# psvsd-v20.net
KiCad netlist of a schematic drawn in EAGLE
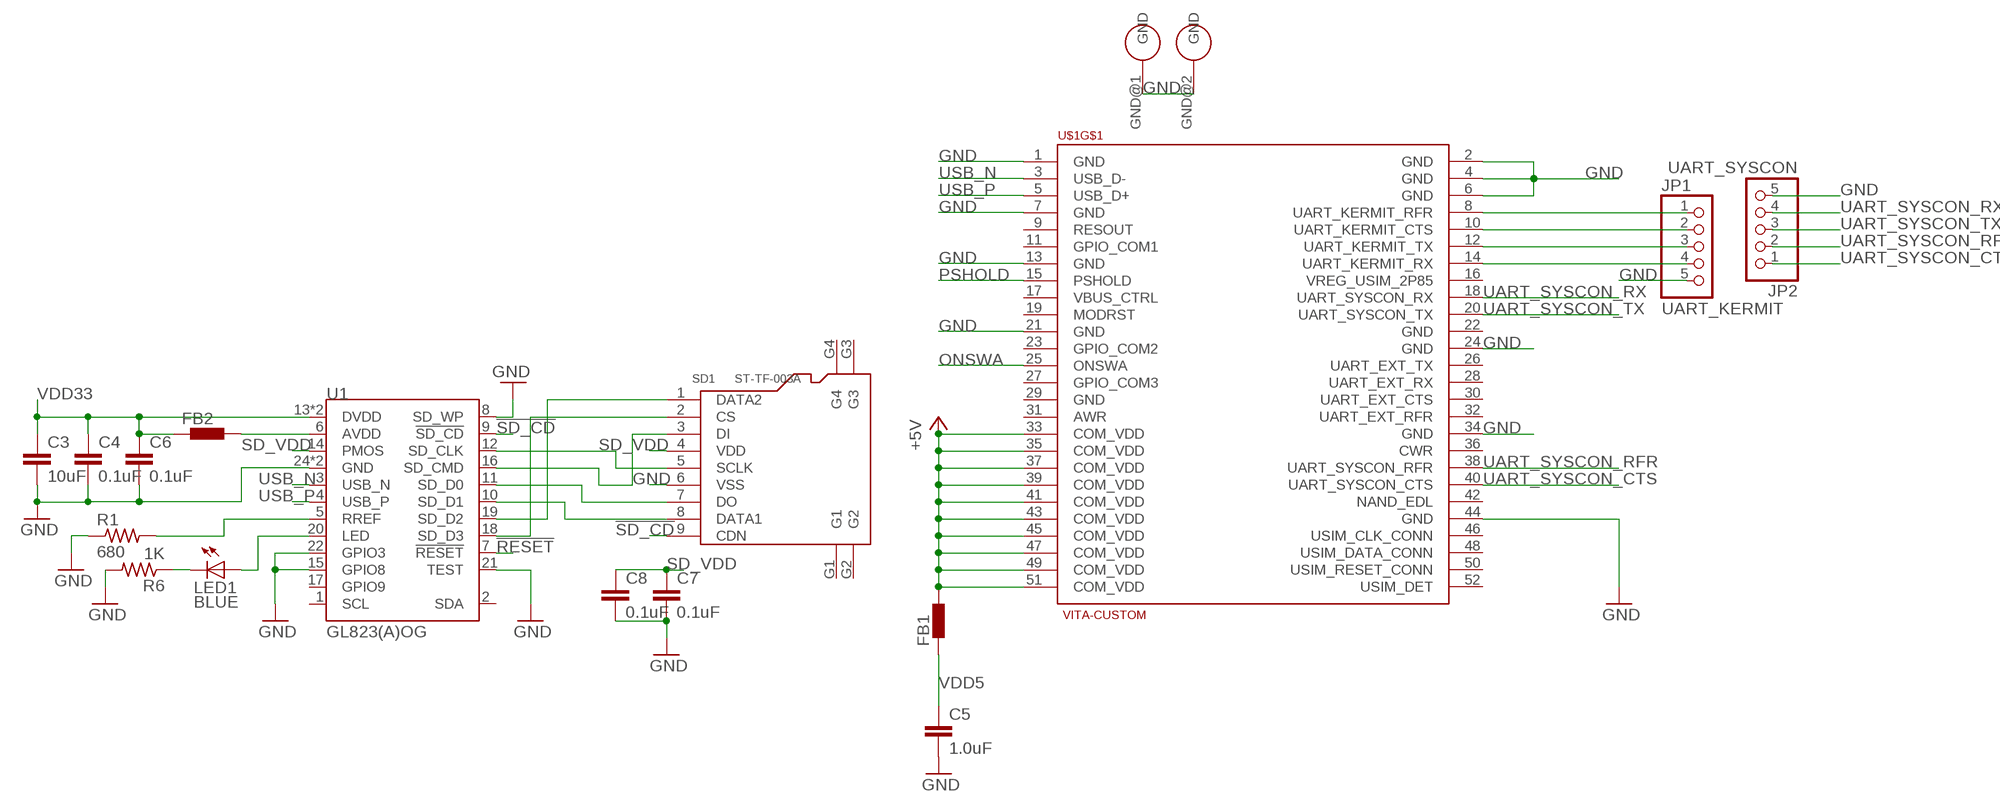
[diagram p0: schematic, sheet 1]
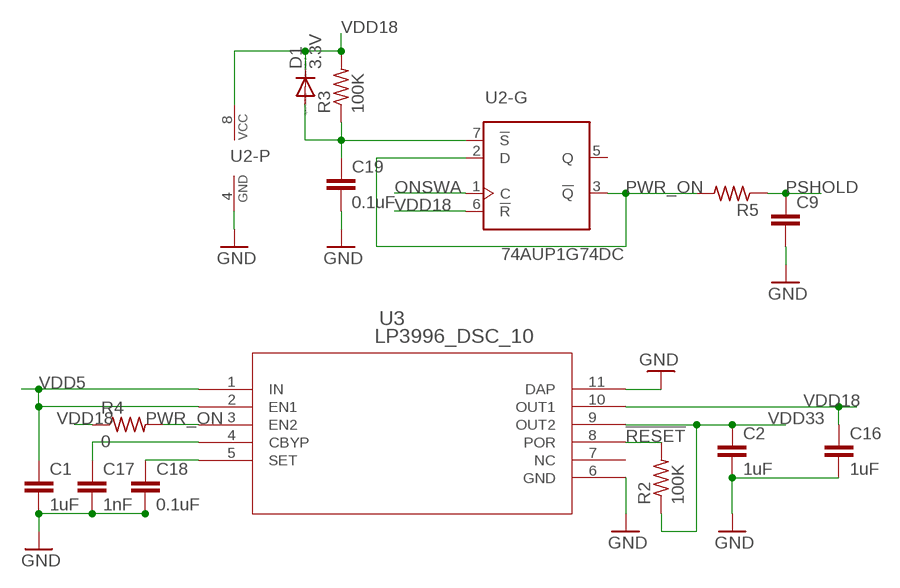
[diagram p1: schematic, sheet 2]

(export (version "E")
  (design (tool "Eeschema 10.0.6"))
  (components
    (comp (ref "C1")
      (value "1uF")
      (footprint "eagle-import:C0603")
      (libsource (lib "eagle-import") (part "C-EUC0603"))
    )
    (comp (ref "C2")
      (value "1uF")
      (footprint "eagle-import:C0603")
      (libsource (lib "eagle-import") (part "C-EUC0603"))
    )
    (comp (ref "C9")
      (value "C-EUC0402")
      (footprint "eagle-import:C0402")
      (libsource (lib "eagle-import") (part "rcl_334_C-EUC0402"))
    )
    (comp (ref "C16")
      (value "1uF")
      (footprint "eagle-import:C0603")
      (libsource (lib "eagle-import") (part "C-EUC0603"))
    )
    (comp (ref "C17")
      (value "1nF")
      (footprint "eagle-import:C0402")
      (libsource (lib "eagle-import") (part "rcl_334_C-EUC0402"))
    )
    (comp (ref "C18")
      (value "0.1uF")
      (footprint "eagle-import:C0402")
      (libsource (lib "eagle-import") (part "resistor_348_C-EUC0402"))
    )
    (comp (ref "C19")
      (value "0.1uF")
      (footprint "eagle-import:C0402")
      (libsource (lib "eagle-import") (part "rcl_334_C-EUC0402"))
    )
    (comp (ref "D1")
      (value "3.3V")
      (footprint "eagle-import:SOD523")
      (libsource (lib "eagle-import") (part "DIODE-SOD523"))
    )
    (comp (ref "R2")
      (value "100K")
      (footprint "eagle-import:R0603")
      (libsource (lib "eagle-import") (part "R-US_R0603"))
    )
    (comp (ref "R3")
      (value "100K")
      (footprint "eagle-import:R0603")
      (libsource (lib "eagle-import") (part "R-US_R0603"))
    )
    (comp (ref "R4")
      (value "0")
      (footprint "eagle-import:R0402")
      (libsource (lib "eagle-import") (part "rcl_334_R-US_R0402"))
    )
    (comp (ref "R5")
      (value "R-US_R0603")
      (footprint "eagle-import:R0603")
      (libsource (lib "eagle-import") (part "rcl_334_R-US_R0603"))
    )
    (comp (ref "U2")
      (value "74AUP1G74DC")
      (footprint "eagle-import:SOT765")
      (libsource (lib "eagle-import") (part "74AUP1G74DC"))
    )
    (comp (ref "U3")
      (value "LP3996_DSC_10")
      (footprint "eagle-import:SDA10A")
      (fields (field (name "PARTNUMBER") "LP3996SD0833"))
      (libsource (lib "eagle-import") (part "LP3996_DSC_10"))
    )
    (comp (ref "C3")
      (value "10uF")
      (footprint "eagle-import:C0402")
      (libsource (lib "eagle-import") (part "rcl_334_C-EUC0402"))
    )
    (comp (ref "C4")
      (value "0.1uF")
      (footprint "eagle-import:C0402")
      (libsource (lib "eagle-import") (part "rcl_334_C-EUC0402"))
    )
    (comp (ref "C5")
      (value "1.0uF")
      (footprint "eagle-import:C0603")
      (libsource (lib "eagle-import") (part "C-EUC0603"))
    )
    (comp (ref "C6")
      (value "0.1uF")
      (footprint "eagle-import:C0402")
      (libsource (lib "eagle-import") (part "rcl_334_C-EUC0402"))
    )
    (comp (ref "C7")
      (value "0.1uF")
      (footprint "eagle-import:C0402")
      (libsource (lib "eagle-import") (part "rcl_334_C-EUC0402"))
    )
    (comp (ref "C8")
      (value "0.1uF")
      (footprint "eagle-import:C0402")
      (libsource (lib "eagle-import") (part "rcl_334_C-EUC0402"))
    )
    (comp (ref "FB1")
      (value "BLM15HB121SN1")
      (footprint "eagle-import:0402")
      (libsource (lib "eagle-import") (part "BLM15HB121SN1"))
    )
    (comp (ref "FB2")
      (value "BLM15HB121SN1")
      (footprint "eagle-import:0402")
      (libsource (lib "eagle-import") (part "inductors_243_BLM15HB121SN1"))
    )
    (comp (ref "JP1")
      (value "UART_KERMIT")
      (footprint "eagle-import:1X05")
      (libsource (lib "eagle-import") (part "PINHD-1X5"))
    )
    (comp (ref "JP2")
      (value "UART_SYSCON")
      (footprint "eagle-import:1X05")
      (libsource (lib "eagle-import") (part "PINHD-1X5"))
    )
    (comp (ref "LED1")
      (value "BLUE")
      (footprint "eagle-import:SML0603")
      (libsource (lib "eagle-import") (part "LEDSML0603"))
    )
    (comp (ref "R1")
      (value "680")
      (footprint "eagle-import:R0603")
      (libsource (lib "eagle-import") (part "rcl_334_R-US_R0603"))
    )
    (comp (ref "R6")
      (value "1K")
      (footprint "eagle-import:R0603")
      (libsource (lib "eagle-import") (part "R-US_R0603"))
    )
    (comp (ref "SD1")
      (value "ST-TF-003A")
      (footprint "eagle-import:MICRO-SD9+4P-SMD-16.1X14.5X1.85MM")
      (libsource (lib "eagle-import") (part "MICRO-SD-CARD-SOCKET-9P(ST-TF-003A)"))
    )
    (comp (ref "U$1")
      (value "VITA-CUSTOM")
      (footprint "eagle-import:VITA-MINI-PCI-E")
      (libsource (lib "eagle-import") (part "VITA-CUSTOM"))
    )
    (comp (ref "U1")
      (value "GL823(A)OG")
      (footprint "eagle-import:QFN-24")
      (libsource (lib "eagle-import") (part "GL823(A)OG"))
    )
  )
  (nets
    (net (code "1") (name "+5V") (class "Default")
      (node (ref "FB1") (pin "2") (pinfunction "2_2") (pintype "passive"))
      (node (ref "U$1") (pin "33") (pinfunction "COM_VDD_33") (pintype "bidirectional"))
      (node (ref "U$1") (pin "35") (pinfunction "COM_VDD_35") (pintype "bidirectional"))
      (node (ref "U$1") (pin "37") (pinfunction "COM_VDD_37") (pintype "bidirectional"))
      (node (ref "U$1") (pin "39") (pinfunction "COM_VDD_39") (pintype "bidirectional"))
      (node (ref "U$1") (pin "41") (pinfunction "COM_VDD_41") (pintype "bidirectional"))
      (node (ref "U$1") (pin "43") (pinfunction "COM_VDD_43") (pintype "bidirectional"))
      (node (ref "U$1") (pin "45") (pinfunction "COM_VDD_45") (pintype "bidirectional"))
      (node (ref "U$1") (pin "47") (pinfunction "COM_VDD_47") (pintype "bidirectional"))
      (node (ref "U$1") (pin "49") (pinfunction "COM_VDD_49") (pintype "bidirectional"))
      (node (ref "U$1") (pin "51") (pinfunction "COM_VDD_51") (pintype "bidirectional"))
    )
    (net (code "2") (name "GND") (class "Default")
      (node (ref "C1") (pin "2") (pinfunction "2_2") (pintype "passive"))
      (node (ref "C16") (pin "2") (pinfunction "2_2") (pintype "passive"))
      (node (ref "C17") (pin "2") (pinfunction "2_2") (pintype "passive"))
      (node (ref "C18") (pin "2") (pinfunction "2_2") (pintype "passive"))
      (node (ref "C19") (pin "2") (pinfunction "2_2") (pintype "passive"))
      (node (ref "C2") (pin "2") (pinfunction "2_2") (pintype "passive"))
      (node (ref "C3") (pin "2") (pinfunction "2_2") (pintype "passive"))
      (node (ref "C4") (pin "2") (pinfunction "2_2") (pintype "passive"))
      (node (ref "C5") (pin "2") (pinfunction "2_2") (pintype "passive"))
      (node (ref "C6") (pin "2") (pinfunction "2_2") (pintype "passive"))
      (node (ref "C7") (pin "2") (pinfunction "2_2") (pintype "passive"))
      (node (ref "C8") (pin "2") (pinfunction "2_2") (pintype "passive"))
      (node (ref "C9") (pin "2") (pinfunction "2_2") (pintype "passive"))
      (node (ref "JP1") (pin "5") (pinfunction "5_5") (pintype "passive"))
      (node (ref "JP2") (pin "5") (pinfunction "5_5") (pintype "passive"))
      (node (ref "R1") (pin "1") (pinfunction "1_1") (pintype "passive"))
      (node (ref "R6") (pin "2") (pinfunction "2_2") (pintype "passive"))
      (node (ref "SD1") (pin "6") (pinfunction "VSS_6") (pintype "bidirectional"))
      (node (ref "U$1") (pin "1") (pinfunction "GND_1") (pintype "bidirectional"))
      (node (ref "U$1") (pin "13") (pinfunction "GND_13") (pintype "bidirectional"))
      (node (ref "U$1") (pin "2") (pinfunction "GND_2") (pintype "bidirectional"))
      (node (ref "U$1") (pin "21") (pinfunction "GND_21") (pintype "bidirectional"))
      (node (ref "U$1") (pin "24") (pinfunction "GND_24") (pintype "bidirectional"))
      (node (ref "U$1") (pin "34") (pinfunction "GND_34") (pintype "bidirectional"))
      (node (ref "U$1") (pin "4") (pinfunction "GND_4") (pintype "bidirectional"))
      (node (ref "U$1") (pin "44") (pinfunction "GND_44") (pintype "bidirectional"))
      (node (ref "U$1") (pin "6") (pinfunction "GND_6") (pintype "bidirectional"))
      (node (ref "U$1") (pin "7") (pinfunction "GND_7") (pintype "bidirectional"))
      (node (ref "U$1") (pin "GND@1") (pinfunction "GND_GND@1") (pintype "power_in"))
      (node (ref "U$1") (pin "GND@2") (pinfunction "GND_GND@2") (pintype "power_in"))
      (node (ref "U1") (pin "15") (pinfunction "GPIO8_15") (pintype "bidirectional"))
      (node (ref "U1") (pin "21") (pinfunction "TEST_21") (pintype "input"))
      (node (ref "U1") (pin "22") (pinfunction "GPIO3_22") (pintype "bidirectional"))
      (node (ref "U1") (pin "24") (pinfunction "GND_24") (pintype "power_in"))
      (node (ref "U1") (pin "25") (pinfunction "GND_25") (pintype "power_in"))
      (node (ref "U1") (pin "8") (pinfunction "SD_WP_8") (pintype "input"))
      (node (ref "U2") (pin "4") (pinfunction "GND_4") (pintype "power_in"))
      (node (ref "U3") (pin "11") (pinfunction "DAP_11") (pintype "passive"))
      (node (ref "U3") (pin "6") (pinfunction "GND_6") (pintype "passive"))
    )
    (net (code "3") (name "Net-(LED1-PadC)") (class "Default")
      (node (ref "LED1") (pin "C") (pinfunction "C_C") (pintype "passive"))
      (node (ref "R6") (pin "1") (pinfunction "1_1") (pintype "passive"))
    )
    (net (code "4") (name "Net-(SD1-CS)") (class "Default")
      (node (ref "SD1") (pin "2") (pinfunction "CS_2") (pintype "bidirectional"))
      (node (ref "U1") (pin "18") (pinfunction "SD_D3_18") (pintype "bidirectional"))
    )
    (net (code "5") (name "Net-(SD1-DATA1)") (class "Default")
      (node (ref "SD1") (pin "8") (pinfunction "DATA1_8") (pintype "bidirectional"))
      (node (ref "U1") (pin "10") (pinfunction "SD_D1_10") (pintype "bidirectional"))
    )
    (net (code "6") (name "Net-(SD1-DATA2)") (class "Default")
      (node (ref "SD1") (pin "1") (pinfunction "DATA2_1") (pintype "bidirectional"))
      (node (ref "U1") (pin "19") (pinfunction "SD_D2_19") (pintype "bidirectional"))
    )
    (net (code "7") (name "Net-(SD1-DI)") (class "Default")
      (node (ref "SD1") (pin "3") (pinfunction "DI_3") (pintype "bidirectional"))
      (node (ref "U1") (pin "16") (pinfunction "SD_CMD_16") (pintype "bidirectional"))
    )
    (net (code "8") (name "Net-(SD1-DO)") (class "Default")
      (node (ref "SD1") (pin "7") (pinfunction "DO_7") (pintype "bidirectional"))
      (node (ref "U1") (pin "11") (pinfunction "SD_D0_11") (pintype "bidirectional"))
    )
    (net (code "9") (name "Net-(SD1-SCLK)") (class "Default")
      (node (ref "SD1") (pin "5") (pinfunction "SCLK_5") (pintype "bidirectional"))
      (node (ref "U1") (pin "12") (pinfunction "SD_CLK_12") (pintype "output"))
    )
    (net (code "10") (name "Net-(U$1A-UART_KERMIT_CTS)") (class "Default")
      (node (ref "JP1") (pin "2") (pinfunction "2_2") (pintype "passive"))
      (node (ref "U$1") (pin "10") (pinfunction "UART_KERMIT_CTS_10") (pintype "bidirectional"))
    )
    (net (code "11") (name "Net-(U$1A-UART_KERMIT_RFR)") (class "Default")
      (node (ref "JP1") (pin "1") (pinfunction "1_1") (pintype "passive"))
      (node (ref "U$1") (pin "8") (pinfunction "UART_KERMIT_RFR_8") (pintype "bidirectional"))
    )
    (net (code "12") (name "Net-(U$1A-UART_KERMIT_RX)") (class "Default")
      (node (ref "JP1") (pin "4") (pinfunction "4_4") (pintype "passive"))
      (node (ref "U$1") (pin "14") (pinfunction "UART_KERMIT_RX_14") (pintype "bidirectional"))
    )
    (net (code "13") (name "Net-(U$1A-UART_KERMIT_TX)") (class "Default")
      (node (ref "JP1") (pin "3") (pinfunction "3_3") (pintype "passive"))
      (node (ref "U$1") (pin "12") (pinfunction "UART_KERMIT_TX_12") (pintype "bidirectional"))
    )
    (net (code "14") (name "Net-(U1-AVDD)") (class "Default")
      (node (ref "FB2") (pin "2") (pinfunction "2_2") (pintype "passive"))
      (node (ref "U1") (pin "6") (pinfunction "AVDD_6") (pintype "power_in"))
    )
    (net (code "15") (name "Net-(U1-LED)") (class "Default")
      (node (ref "LED1") (pin "A") (pinfunction "A_A") (pintype "passive"))
      (node (ref "U1") (pin "20") (pinfunction "LED_20") (pintype "output"))
    )
    (net (code "16") (name "Net-(U1-RREF)") (class "Default")
      (node (ref "R1") (pin "2") (pinfunction "2_2") (pintype "passive"))
      (node (ref "U1") (pin "5") (pinfunction "RREF_5") (pintype "bidirectional"))
    )
    (net (code "17") (name "Net-(U2A-~{S})") (class "Default")
      (node (ref "C19") (pin "1") (pinfunction "1_1") (pintype "passive"))
      (node (ref "D1") (pin "A") (pinfunction "A_A") (pintype "passive"))
      (node (ref "R3") (pin "1") (pinfunction "1_1") (pintype "passive"))
      (node (ref "U2") (pin "7") (pinfunction "~{S}_7") (pintype "input"))
    )
    (net (code "18") (name "Net-(U3-CBYP)") (class "Default")
      (node (ref "C17") (pin "1") (pinfunction "1_1") (pintype "passive"))
      (node (ref "U3") (pin "4") (pinfunction "CBYP_4") (pintype "passive"))
    )
    (net (code "19") (name "Net-(U3-SET)") (class "Default")
      (node (ref "C18") (pin "1") (pinfunction "1_1") (pintype "passive"))
      (node (ref "U3") (pin "5") (pinfunction "SET_5") (pintype "passive"))
    )
    (net (code "20") (name "ONSWA") (class "Default")
      (node (ref "U$1") (pin "25") (pinfunction "ONSWA_25") (pintype "bidirectional"))
      (node (ref "U2") (pin "1") (pinfunction "C_1") (pintype "input"))
    )
    (net (code "21") (name "PSHOLD") (class "Default")
      (node (ref "C9") (pin "1") (pinfunction "1_1") (pintype "passive"))
      (node (ref "R5") (pin "1") (pinfunction "1_1") (pintype "passive"))
      (node (ref "U$1") (pin "15") (pinfunction "PSHOLD_15") (pintype "bidirectional"))
    )
    (net (code "22") (name "PWR_ON") (class "Default")
      (node (ref "R4") (pin "2") (pinfunction "2_2") (pintype "passive"))
      (node (ref "R5") (pin "2") (pinfunction "2_2") (pintype "passive"))
      (node (ref "U2") (pin "2") (pinfunction "D_2") (pintype "input"))
      (node (ref "U2") (pin "3") (pinfunction "~{Q}_3") (pintype "output"))
      (node (ref "U3") (pin "3") (pinfunction "EN2_3") (pintype "passive"))
    )
    (net (code "23") (name "SD_VDD") (class "Default")
      (node (ref "C7") (pin "1") (pinfunction "1_1") (pintype "passive"))
      (node (ref "C8") (pin "1") (pinfunction "1_1") (pintype "passive"))
      (node (ref "SD1") (pin "4") (pinfunction "VDD_4") (pintype "bidirectional"))
      (node (ref "U1") (pin "14") (pinfunction "PMOS_14") (pintype "power_in"))
    )
    (net (code "24") (name "UART_SYSCON_CTS") (class "Default")
      (node (ref "JP2") (pin "1") (pinfunction "1_1") (pintype "passive"))
      (node (ref "U$1") (pin "40") (pinfunction "UART_SYSCON_CTS_40") (pintype "bidirectional"))
    )
    (net (code "25") (name "UART_SYSCON_RFR") (class "Default")
      (node (ref "JP2") (pin "2") (pinfunction "2_2") (pintype "passive"))
      (node (ref "U$1") (pin "38") (pinfunction "UART_SYSCON_RFR_38") (pintype "bidirectional"))
    )
    (net (code "26") (name "UART_SYSCON_RX") (class "Default")
      (node (ref "JP2") (pin "4") (pinfunction "4_4") (pintype "passive"))
      (node (ref "U$1") (pin "18") (pinfunction "UART_SYSCON_RX_18") (pintype "bidirectional"))
    )
    (net (code "27") (name "UART_SYSCON_TX") (class "Default")
      (node (ref "JP2") (pin "3") (pinfunction "3_3") (pintype "passive"))
      (node (ref "U$1") (pin "20") (pinfunction "UART_SYSCON_TX_20") (pintype "bidirectional"))
    )
    (net (code "28") (name "USB_N") (class "Default")
      (node (ref "U$1") (pin "3") (pinfunction "USB_D-_3") (pintype "bidirectional"))
      (node (ref "U1") (pin "3") (pinfunction "USB_N_3") (pintype "bidirectional"))
    )
    (net (code "29") (name "USB_P") (class "Default")
      (node (ref "U$1") (pin "5") (pinfunction "USB_D+_5") (pintype "bidirectional"))
      (node (ref "U1") (pin "4") (pinfunction "USB_P_4") (pintype "bidirectional"))
    )
    (net (code "30") (name "VDD5") (class "Default")
      (node (ref "C1") (pin "1") (pinfunction "1_1") (pintype "passive"))
      (node (ref "C5") (pin "1") (pinfunction "1_1") (pintype "passive"))
      (node (ref "FB1") (pin "1") (pinfunction "1_1") (pintype "passive"))
      (node (ref "U3") (pin "1") (pinfunction "IN_1") (pintype "input"))
      (node (ref "U3") (pin "2") (pinfunction "EN1_2") (pintype "passive"))
    )
    (net (code "31") (name "VDD18") (class "Default")
      (node (ref "C16") (pin "1") (pinfunction "1_1") (pintype "passive"))
      (node (ref "D1") (pin "C") (pinfunction "C_C") (pintype "passive"))
      (node (ref "R3") (pin "2") (pinfunction "2_2") (pintype "passive"))
      (node (ref "R4") (pin "1") (pinfunction "1_1") (pintype "passive"))
      (node (ref "U2") (pin "6") (pinfunction "~{R}_6") (pintype "input"))
      (node (ref "U2") (pin "8") (pinfunction "VCC_8") (pintype "power_in"))
      (node (ref "U3") (pin "10") (pinfunction "OUT1_10") (pintype "output"))
    )
    (net (code "32") (name "VDD33") (class "Default")
      (node (ref "C2") (pin "1") (pinfunction "1_1") (pintype "passive"))
      (node (ref "C3") (pin "1") (pinfunction "1_1") (pintype "passive"))
      (node (ref "C4") (pin "1") (pinfunction "1_1") (pintype "passive"))
      (node (ref "C6") (pin "1") (pinfunction "1_1") (pintype "passive"))
      (node (ref "FB2") (pin "1") (pinfunction "1_1") (pintype "passive"))
      (node (ref "R2") (pin "1") (pinfunction "1_1") (pintype "passive"))
      (node (ref "U1") (pin "13") (pinfunction "DVDD_13") (pintype "power_in"))
      (node (ref "U1") (pin "23") (pinfunction "DVDD_23") (pintype "power_in"))
      (node (ref "U3") (pin "9") (pinfunction "OUT2_9") (pintype "output"))
    )
    (net (code "33") (name "unconnected-(SD1-PadG1)") (class "Default")
      (node (ref "SD1") (pin "G1") (pinfunction "G1_G1") (pintype "bidirectional"))
    )
    (net (code "34") (name "unconnected-(SD1-PadG2)") (class "Default")
      (node (ref "SD1") (pin "G2") (pinfunction "G2_G2") (pintype "bidirectional"))
    )
    (net (code "35") (name "unconnected-(SD1-PadG3)") (class "Default")
      (node (ref "SD1") (pin "G3") (pinfunction "G3_G3") (pintype "bidirectional"))
    )
    (net (code "36") (name "unconnected-(SD1-PadG4)") (class "Default")
      (node (ref "SD1") (pin "G4") (pinfunction "G4_G4") (pintype "bidirectional"))
    )
    (net (code "37") (name "unconnected-(U$1A-AWR-Pad31)") (class "Default")
      (node (ref "U$1") (pin "31") (pinfunction "AWR_31") (pintype "bidirectional"))
    )
    (net (code "38") (name "unconnected-(U$1A-CWR-Pad36)") (class "Default")
      (node (ref "U$1") (pin "36") (pinfunction "CWR_36") (pintype "bidirectional"))
    )
    (net (code "39") (name "unconnected-(U$1A-GND-Pad22)") (class "Default")
      (node (ref "U$1") (pin "22") (pinfunction "GND_22") (pintype "bidirectional"))
    )
    (net (code "40") (name "unconnected-(U$1A-GND-Pad29)") (class "Default")
      (node (ref "U$1") (pin "29") (pinfunction "GND_29") (pintype "bidirectional"))
    )
    (net (code "41") (name "unconnected-(U$1A-GPIO_COM1-Pad11)") (class "Default")
      (node (ref "U$1") (pin "11") (pinfunction "GPIO_COM1_11") (pintype "bidirectional"))
    )
    (net (code "42") (name "unconnected-(U$1A-GPIO_COM2-Pad23)") (class "Default")
      (node (ref "U$1") (pin "23") (pinfunction "GPIO_COM2_23") (pintype "bidirectional"))
    )
    (net (code "43") (name "unconnected-(U$1A-GPIO_COM3-Pad27)") (class "Default")
      (node (ref "U$1") (pin "27") (pinfunction "GPIO_COM3_27") (pintype "bidirectional"))
    )
    (net (code "44") (name "unconnected-(U$1A-MODRST-Pad19)") (class "Default")
      (node (ref "U$1") (pin "19") (pinfunction "MODRST_19") (pintype "bidirectional"))
    )
    (net (code "45") (name "unconnected-(U$1A-NAND_EDL-Pad42)") (class "Default")
      (node (ref "U$1") (pin "42") (pinfunction "NAND_EDL_42") (pintype "bidirectional"))
    )
    (net (code "46") (name "unconnected-(U$1A-RESOUT-Pad9)") (class "Default")
      (node (ref "U$1") (pin "9") (pinfunction "RESOUT_9") (pintype "bidirectional"))
    )
    (net (code "47") (name "unconnected-(U$1A-UART_EXT_CTS-Pad30)") (class "Default")
      (node (ref "U$1") (pin "30") (pinfunction "UART_EXT_CTS_30") (pintype "bidirectional"))
    )
    (net (code "48") (name "unconnected-(U$1A-UART_EXT_RFR-Pad32)") (class "Default")
      (node (ref "U$1") (pin "32") (pinfunction "UART_EXT_RFR_32") (pintype "bidirectional"))
    )
    (net (code "49") (name "unconnected-(U$1A-UART_EXT_RX-Pad28)") (class "Default")
      (node (ref "U$1") (pin "28") (pinfunction "UART_EXT_RX_28") (pintype "bidirectional"))
    )
    (net (code "50") (name "unconnected-(U$1A-UART_EXT_TX-Pad26)") (class "Default")
      (node (ref "U$1") (pin "26") (pinfunction "UART_EXT_TX_26") (pintype "bidirectional"))
    )
    (net (code "51") (name "unconnected-(U$1A-USIM_CLK_CONN-Pad46)") (class "Default")
      (node (ref "U$1") (pin "46") (pinfunction "USIM_CLK_CONN_46") (pintype "bidirectional"))
    )
    (net (code "52") (name "unconnected-(U$1A-USIM_DATA_CONN-Pad48)") (class "Default")
      (node (ref "U$1") (pin "48") (pinfunction "USIM_DATA_CONN_48") (pintype "bidirectional"))
    )
    (net (code "53") (name "unconnected-(U$1A-USIM_DET-Pad52)") (class "Default")
      (node (ref "U$1") (pin "52") (pinfunction "USIM_DET_52") (pintype "bidirectional"))
    )
    (net (code "54") (name "unconnected-(U$1A-USIM_RESET_CONN-Pad50)") (class "Default")
      (node (ref "U$1") (pin "50") (pinfunction "USIM_RESET_CONN_50") (pintype "bidirectional"))
    )
    (net (code "55") (name "unconnected-(U$1A-VBUS_CTRL-Pad17)") (class "Default")
      (node (ref "U$1") (pin "17") (pinfunction "VBUS_CTRL_17") (pintype "bidirectional"))
    )
    (net (code "56") (name "unconnected-(U$1A-VREG_USIM_2P85-Pad16)") (class "Default")
      (node (ref "U$1") (pin "16") (pinfunction "VREG_USIM_2P85_16") (pintype "bidirectional"))
    )
    (net (code "57") (name "unconnected-(U1-GPIO9-Pad17)") (class "Default")
      (node (ref "U1") (pin "17") (pinfunction "GPIO9_17") (pintype "bidirectional"))
    )
    (net (code "58") (name "unconnected-(U1-SCL-Pad1)") (class "Default")
      (node (ref "U1") (pin "1") (pinfunction "SCL_1") (pintype "bidirectional"))
    )
    (net (code "59") (name "unconnected-(U1-SDA-Pad2)") (class "Default")
      (node (ref "U1") (pin "2") (pinfunction "SDA_2") (pintype "bidirectional"))
    )
    (net (code "60") (name "unconnected-(U2A-Q-Pad5)") (class "Default")
      (node (ref "U2") (pin "5") (pinfunction "Q_5") (pintype "output"))
    )
    (net (code "61") (name "unconnected-(U3-NC-Pad7)") (class "Default")
      (node (ref "U3") (pin "7") (pinfunction "NC_7") (pintype "passive"))
    )
    (net (code "62") (name "~{RESET}") (class "Default")
      (node (ref "R2") (pin "2") (pinfunction "2_2") (pintype "passive"))
      (node (ref "U1") (pin "7") (pinfunction "~{RESET}_7") (pintype "input"))
      (node (ref "U3") (pin "8") (pinfunction "POR_8") (pintype "passive"))
    )
    (net (code "63") (name "~{SD_CD}") (class "Default")
      (node (ref "SD1") (pin "9") (pinfunction "CDN_9") (pintype "bidirectional"))
      (node (ref "U1") (pin "9") (pinfunction "~{SD_CD}_9") (pintype "input"))
    )
  )
)
